# RelayWing.net
KiCad netlist of a schematic drawn in EAGLE
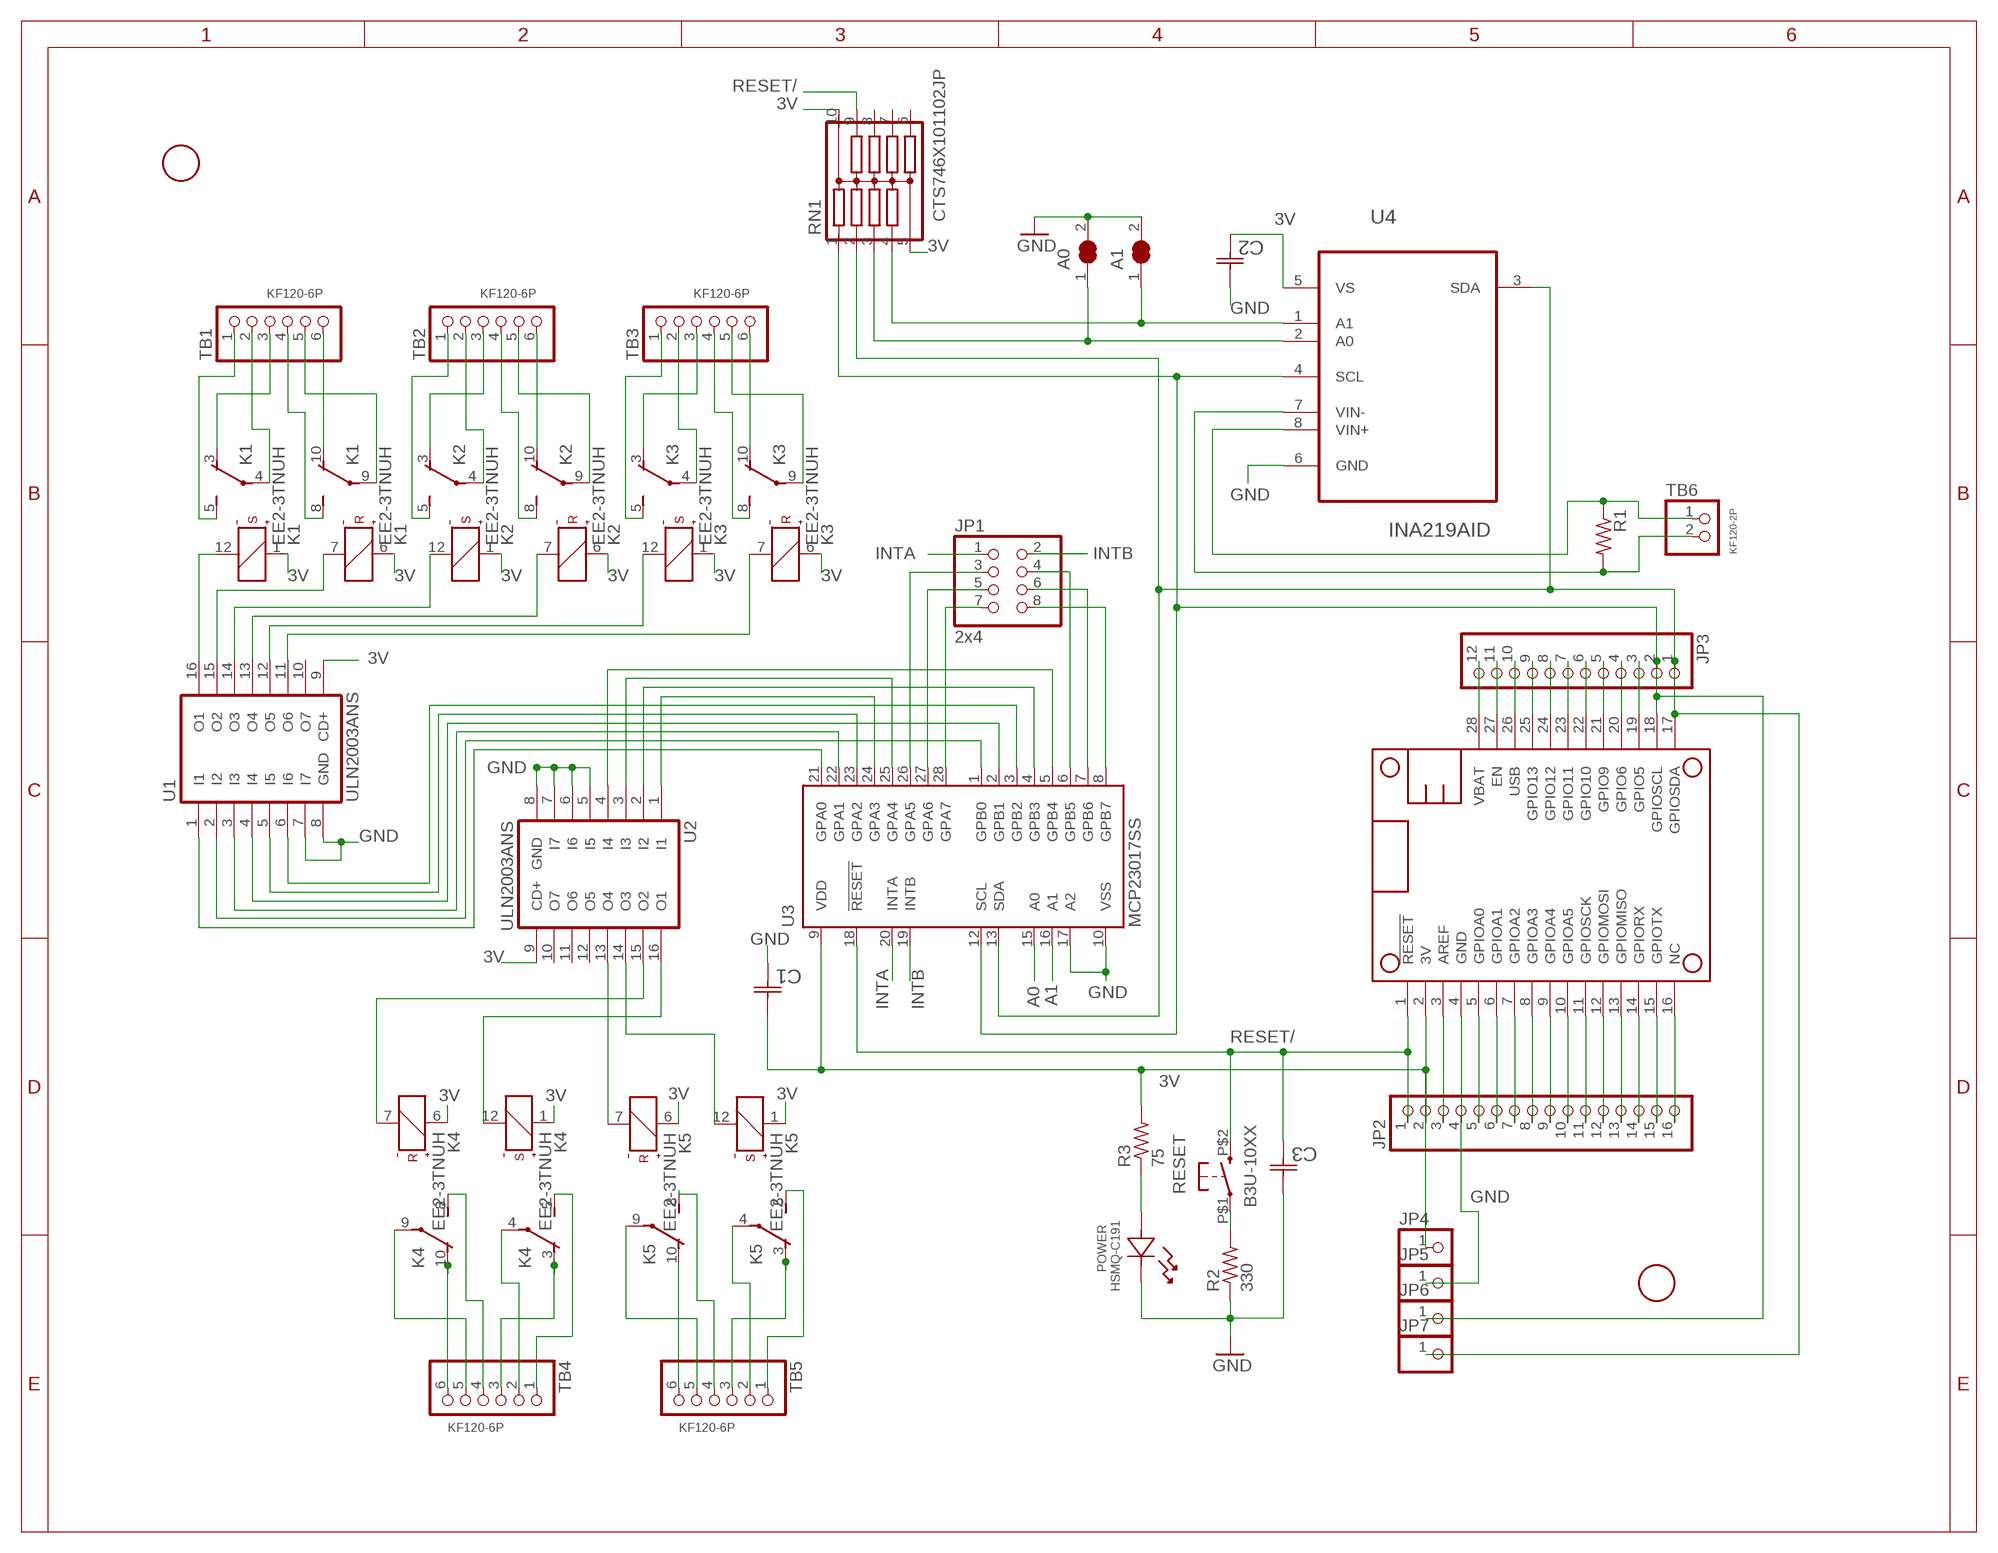
[diagram p0: schematic, sheet 1]

(export (version "E")
  (design (tool "Eeschema 10.0.6"))
  (components
    (comp (ref "A0")
      (value "SJW-SHORTED")
      (footprint "eagle-import:SJW-SHORTED")
      (libsource (lib "eagle-import") (part "SJW-SHORTED"))
    )
    (comp (ref "A1")
      (value "SJW-SHORTED")
      (footprint "eagle-import:SJW-SHORTED")
      (libsource (lib "eagle-import") (part "SJW-SHORTED"))
    )
    (comp (ref "C1")
      (value "MUR-1220-CAP")
      (footprint "eagle-import:CAPC2012")
      (libsource (lib "eagle-import") (part "MUR-1220-CAP"))
    )
    (comp (ref "C2")
      (value "MUR-1220-CAP")
      (footprint "eagle-import:CAPC2012")
      (libsource (lib "eagle-import") (part "MUR-1220-CAP"))
    )
    (comp (ref "C3")
      (value "MUR-1220-CAP")
      (footprint "eagle-import:CAPC2012")
      (libsource (lib "eagle-import") (part "MUR-1220-CAP"))
    )
    (comp (ref "JP1")
      (value "2x4")
      (footprint "eagle-import:2X04")
      (libsource (lib "eagle-import") (part "PINHD-2X4"))
    )
    (comp (ref "JP2")
      (value "PINHD-1X16")
      (footprint "eagle-import:1X16")
      (libsource (lib "eagle-import") (part "PINHD-1X16"))
    )
    (comp (ref "JP3")
      (value "PINHD-1X12")
      (footprint "eagle-import:1X12")
      (libsource (lib "eagle-import") (part "PINHD-1X12"))
    )
    (comp (ref "JP4")
      (value "PINHD-1X1CB")
      (footprint "eagle-import:1X01-CLEANBIG")
      (libsource (lib "eagle-import") (part "PINHD-1X1CB"))
    )
    (comp (ref "JP5")
      (value "PINHD-1X1CB")
      (footprint "eagle-import:1X01-CLEANBIG")
      (libsource (lib "eagle-import") (part "PINHD-1X1CB"))
    )
    (comp (ref "JP6")
      (value "PINHD-1X1CB")
      (footprint "eagle-import:1X01-CLEANBIG")
      (libsource (lib "eagle-import") (part "PINHD-1X1CB"))
    )
    (comp (ref "JP7")
      (value "PINHD-1X1CB")
      (footprint "eagle-import:1X01-CLEANBIG")
      (libsource (lib "eagle-import") (part "PINHD-1X1CB"))
    )
    (comp (ref "K1")
      (value "EE2-3TNUH")
      (footprint "eagle-import:NUH")
      (libsource (lib "eagle-import") (part "EE2-T?NUH3"))
    )
    (comp (ref "K2")
      (value "EE2-3TNUH")
      (footprint "eagle-import:NUH")
      (libsource (lib "eagle-import") (part "EE2-T?NUH3"))
    )
    (comp (ref "K3")
      (value "EE2-3TNUH")
      (footprint "eagle-import:NUH")
      (libsource (lib "eagle-import") (part "EE2-T?NUH3"))
    )
    (comp (ref "K4")
      (value "EE2-3TNUH")
      (footprint "eagle-import:NUH")
      (libsource (lib "eagle-import") (part "EE2-T?NUH3"))
    )
    (comp (ref "K5")
      (value "EE2-3TNUH")
      (footprint "eagle-import:NUH")
      (libsource (lib "eagle-import") (part "EE2-T?NUH3"))
    )
    (comp (ref "MS1")
      (value "FEATHERWING_NODIM")
      (footprint "eagle-import:FEATHERWING_DIM")
      (libsource (lib "eagle-import") (part "FEATHERWING_NODIM"))
    )
    (comp (ref "POWER")
      (value "HSMQ-C191")
      (footprint "eagle-import:LED3_HSMX-C120")
      (fields (field (name "MANUFACTURER_PART_NUMBER") "HSMQC191"))
      (libsource (lib "eagle-import") (part "HSMQ-C191"))
    )
    (comp (ref "R1")
      (value "0.1")
      (footprint "eagle-import:M3216")
      (libsource (lib "eagle-import") (part "resistor_348_R-US_M3216"))
    )
    (comp (ref "R2")
      (value "330")
      (footprint "eagle-import:R0603")
      (libsource (lib "eagle-import") (part "R-US_R0603"))
    )
    (comp (ref "R3")
      (value "75")
      (footprint "eagle-import:R0603")
      (libsource (lib "eagle-import") (part "R-US_R0603"))
    )
    (comp (ref "RESET")
      (value "B3U-10XX")
      (footprint "eagle-import:B3U-10XX")
      (libsource (lib "eagle-import") (part "B3U-10XX"))
    )
    (comp (ref "RN1")
      (value "CTS746X101102JP")
      (footprint "eagle-import:CTS746X101")
      (libsource (lib "eagle-import") (part "CTS746X"))
    )
    (comp (ref "TB1")
      (value "KF120-6P")
      (footprint "eagle-import:KF120-6P_ROUND")
      (libsource (lib "eagle-import") (part "KF120-6P"))
    )
    (comp (ref "TB2")
      (value "KF120-6P")
      (footprint "eagle-import:KF120-6P_ROUND")
      (libsource (lib "eagle-import") (part "KF120-6P"))
    )
    (comp (ref "TB3")
      (value "KF120-6P")
      (footprint "eagle-import:KF120-6P_ROUND")
      (libsource (lib "eagle-import") (part "KF120-6P"))
    )
    (comp (ref "TB4")
      (value "KF120-6P")
      (footprint "eagle-import:KF120-6P_ROUND")
      (libsource (lib "eagle-import") (part "KF120-6P"))
    )
    (comp (ref "TB5")
      (value "KF120-6P")
      (footprint "eagle-import:KF120-6P_ROUND")
      (libsource (lib "eagle-import") (part "KF120-6P"))
    )
    (comp (ref "TB6")
      (value "KF120-2P")
      (footprint "eagle-import:KF120-2P_ROUND")
      (libsource (lib "eagle-import") (part "KF120-2P"))
    )
    (comp (ref "U$2")
      (value "FIDUCIAL")
      (footprint "eagle-import:FIDUCIAL_1MM")
      (libsource (lib "eagle-import") (part "FIDUCIAL"))
    )
    (comp (ref "U$3")
      (value "FIDUCIAL")
      (footprint "eagle-import:FIDUCIAL_1MM")
      (libsource (lib "eagle-import") (part "FIDUCIAL"))
    )
    (comp (ref "U1")
      (value "ULN2003ANS")
      (footprint "eagle-import:SO16-NS")
      (libsource (lib "eagle-import") (part "ULN2003ANS"))
    )
    (comp (ref "U2")
      (value "ULN2003ANS")
      (footprint "eagle-import:SO16-NS")
      (libsource (lib "eagle-import") (part "ULN2003ANS"))
    )
    (comp (ref "U3")
      (value "MCP23017SS")
      (footprint "eagle-import:SSOP28")
      (fields (field (name "MF") "MICROCHIP") (field (name "MPN") "MCP23017-E/SS"))
      (libsource (lib "eagle-import") (part "MCP23017SS"))
    )
    (comp (ref "U4")
      (value "INA219AID")
      (footprint "eagle-import:SOIC127P600X175-8N")
      (libsource (lib "eagle-import") (part "INA219AID"))
    )
  )
  (nets
    (net (code "1") (name "/3V") (class "Default")
      (node (ref "C1") (pin "1") (pinfunction "C1_1") (pintype "passive"))
      (node (ref "C2") (pin "2") (pinfunction "C2_2") (pintype "passive"))
      (node (ref "JP2") (pin "2") (pinfunction "2_2") (pintype "passive"))
      (node (ref "JP4") (pin "1") (pinfunction "1_1") (pintype "passive"))
      (node (ref "K1") (pin "1") (pinfunction "+_1") (pintype "passive"))
      (node (ref "K1") (pin "6") (pinfunction "+_6") (pintype "passive"))
      (node (ref "K2") (pin "1") (pinfunction "+_1") (pintype "passive"))
      (node (ref "K2") (pin "6") (pinfunction "+_6") (pintype "passive"))
      (node (ref "K3") (pin "1") (pinfunction "+_1") (pintype "passive"))
      (node (ref "K3") (pin "6") (pinfunction "+_6") (pintype "passive"))
      (node (ref "K4") (pin "1") (pinfunction "+_1") (pintype "passive"))
      (node (ref "K4") (pin "6") (pinfunction "+_6") (pintype "passive"))
      (node (ref "K5") (pin "1") (pinfunction "+_1") (pintype "passive"))
      (node (ref "K5") (pin "6") (pinfunction "+_6") (pintype "passive"))
      (node (ref "MS1") (pin "2") (pinfunction "3V_2") (pintype "power_in"))
      (node (ref "R3") (pin "2") (pinfunction "2_2") (pintype "passive"))
      (node (ref "RN1") (pin "10") (pinfunction "10C_10") (pintype "passive"))
      (node (ref "RN1") (pin "5") (pinfunction "5C_5") (pintype "passive"))
      (node (ref "U1") (pin "9") (pinfunction "CD+_9") (pintype "passive"))
      (node (ref "U2") (pin "9") (pinfunction "CD+_9") (pintype "passive"))
      (node (ref "U3") (pin "9") (pinfunction "VDD_9") (pintype "power_in"))
      (node (ref "U4") (pin "5") (pinfunction "VS_5") (pintype "power_in"))
    )
    (net (code "2") (name "/A0") (class "Default")
      (node (ref "A0") (pin "1") (pinfunction "1_1") (pintype "passive"))
      (node (ref "RN1") (pin "3") (pinfunction "3_3") (pintype "passive"))
      (node (ref "U3") (pin "15") (pinfunction "A0_15") (pintype "input"))
      (node (ref "U4") (pin "2") (pinfunction "A0_2") (pintype "input"))
    )
    (net (code "3") (name "/A1") (class "Default")
      (node (ref "A1") (pin "1") (pinfunction "1_1") (pintype "passive"))
      (node (ref "RN1") (pin "4") (pinfunction "4_4") (pintype "passive"))
      (node (ref "U3") (pin "16") (pinfunction "A1_16") (pintype "input"))
      (node (ref "U4") (pin "1") (pinfunction "A1_1") (pintype "input"))
    )
    (net (code "4") (name "/INTA") (class "Default")
      (node (ref "JP1") (pin "1") (pinfunction "1_1") (pintype "passive"))
      (node (ref "U3") (pin "20") (pinfunction "INTA_20") (pintype "output"))
    )
    (net (code "5") (name "/INTB") (class "Default")
      (node (ref "JP1") (pin "2") (pinfunction "2_2") (pintype "passive"))
      (node (ref "U3") (pin "19") (pinfunction "INTB_19") (pintype "output"))
    )
    (net (code "6") (name "/RESET{slash}") (class "Default")
      (node (ref "C3") (pin "2") (pinfunction "C2_2") (pintype "passive"))
      (node (ref "JP2") (pin "1") (pinfunction "1_1") (pintype "passive"))
      (node (ref "MS1") (pin "1") (pinfunction "~{RESET}_1") (pintype "input"))
      (node (ref "RESET") (pin "P$2") (pinfunction "S_P$2") (pintype "passive"))
      (node (ref "RN1") (pin "9") (pinfunction "9_9") (pintype "passive"))
      (node (ref "U3") (pin "18") (pinfunction "~{RESET}_18") (pintype "input"))
    )
    (net (code "7") (name "GND") (class "Default")
      (node (ref "A0") (pin "2") (pinfunction "2_2") (pintype "passive"))
      (node (ref "A1") (pin "2") (pinfunction "2_2") (pintype "passive"))
      (node (ref "C1") (pin "2") (pinfunction "C2_2") (pintype "passive"))
      (node (ref "C2") (pin "1") (pinfunction "C1_1") (pintype "passive"))
      (node (ref "C3") (pin "1") (pinfunction "C1_1") (pintype "passive"))
      (node (ref "JP2") (pin "4") (pinfunction "4_4") (pintype "passive"))
      (node (ref "JP5") (pin "1") (pinfunction "1_1") (pintype "passive"))
      (node (ref "MS1") (pin "4") (pinfunction "GND_4") (pintype "power_in"))
      (node (ref "POWER") (pin "1") (pinfunction "11_1") (pintype "passive"))
      (node (ref "R2") (pin "1") (pinfunction "1_1") (pintype "passive"))
      (node (ref "U1") (pin "7") (pinfunction "I7_7") (pintype "input"))
      (node (ref "U1") (pin "8") (pinfunction "GND_8") (pintype "power_in"))
      (node (ref "U2") (pin "5") (pinfunction "I5_5") (pintype "input"))
      (node (ref "U2") (pin "6") (pinfunction "I6_6") (pintype "input"))
      (node (ref "U2") (pin "7") (pinfunction "I7_7") (pintype "input"))
      (node (ref "U2") (pin "8") (pinfunction "GND_8") (pintype "power_in"))
      (node (ref "U3") (pin "10") (pinfunction "VSS_10") (pintype "power_in"))
      (node (ref "U3") (pin "17") (pinfunction "A2_17") (pintype "input"))
      (node (ref "U4") (pin "6") (pinfunction "GND_6") (pintype "passive"))
    )
    (net (code "8") (name "Net-(K1A-O)") (class "Default")
      (node (ref "K1") (pin "3") (pinfunction "O_3") (pintype "passive"))
      (node (ref "TB1") (pin "3") (pinfunction "3_3") (pintype "passive"))
    )
    (net (code "9") (name "Net-(K1A-P)") (class "Default")
      (node (ref "K1") (pin "4") (pinfunction "P_4") (pintype "passive"))
      (node (ref "TB1") (pin "2") (pinfunction "2_2") (pintype "passive"))
    )
    (net (code "10") (name "Net-(K1A-S)") (class "Default")
      (node (ref "K1") (pin "5") (pinfunction "S_5") (pintype "passive"))
      (node (ref "TB1") (pin "1") (pinfunction "1_1") (pintype "passive"))
    )
    (net (code "11") (name "Net-(K1B-O)") (class "Default")
      (node (ref "K1") (pin "10") (pinfunction "O_10") (pintype "passive"))
      (node (ref "TB1") (pin "6") (pinfunction "6_6") (pintype "passive"))
    )
    (net (code "12") (name "Net-(K1B-P)") (class "Default")
      (node (ref "K1") (pin "9") (pinfunction "P_9") (pintype "passive"))
      (node (ref "TB1") (pin "5") (pinfunction "5_5") (pintype "passive"))
    )
    (net (code "13") (name "Net-(K1B-S)") (class "Default")
      (node (ref "K1") (pin "8") (pinfunction "S_8") (pintype "passive"))
      (node (ref "TB1") (pin "4") (pinfunction "4_4") (pintype "passive"))
    )
    (net (code "14") (name "Net-(K1C--)") (class "Default")
      (node (ref "K1") (pin "7") (pinfunction "-_7") (pintype "passive"))
      (node (ref "U1") (pin "15") (pinfunction "O2_15") (pintype "open_collector"))
    )
    (net (code "15") (name "Net-(K1D--)") (class "Default")
      (node (ref "K1") (pin "12") (pinfunction "-_12") (pintype "passive"))
      (node (ref "U1") (pin "16") (pinfunction "O1_16") (pintype "open_collector"))
    )
    (net (code "16") (name "Net-(K2A-O)") (class "Default")
      (node (ref "K2") (pin "3") (pinfunction "O_3") (pintype "passive"))
      (node (ref "TB2") (pin "3") (pinfunction "3_3") (pintype "passive"))
    )
    (net (code "17") (name "Net-(K2A-P)") (class "Default")
      (node (ref "K2") (pin "4") (pinfunction "P_4") (pintype "passive"))
      (node (ref "TB2") (pin "2") (pinfunction "2_2") (pintype "passive"))
    )
    (net (code "18") (name "Net-(K2A-S)") (class "Default")
      (node (ref "K2") (pin "5") (pinfunction "S_5") (pintype "passive"))
      (node (ref "TB2") (pin "1") (pinfunction "1_1") (pintype "passive"))
    )
    (net (code "19") (name "Net-(K2B-O)") (class "Default")
      (node (ref "K2") (pin "10") (pinfunction "O_10") (pintype "passive"))
      (node (ref "TB2") (pin "6") (pinfunction "6_6") (pintype "passive"))
    )
    (net (code "20") (name "Net-(K2B-P)") (class "Default")
      (node (ref "K2") (pin "9") (pinfunction "P_9") (pintype "passive"))
      (node (ref "TB2") (pin "5") (pinfunction "5_5") (pintype "passive"))
    )
    (net (code "21") (name "Net-(K2B-S)") (class "Default")
      (node (ref "K2") (pin "8") (pinfunction "S_8") (pintype "passive"))
      (node (ref "TB2") (pin "4") (pinfunction "4_4") (pintype "passive"))
    )
    (net (code "22") (name "Net-(K2C--)") (class "Default")
      (node (ref "K2") (pin "7") (pinfunction "-_7") (pintype "passive"))
      (node (ref "U1") (pin "13") (pinfunction "O4_13") (pintype "open_collector"))
    )
    (net (code "23") (name "Net-(K2D--)") (class "Default")
      (node (ref "K2") (pin "12") (pinfunction "-_12") (pintype "passive"))
      (node (ref "U1") (pin "14") (pinfunction "O3_14") (pintype "open_collector"))
    )
    (net (code "24") (name "Net-(K3A-O)") (class "Default")
      (node (ref "K3") (pin "3") (pinfunction "O_3") (pintype "passive"))
      (node (ref "TB3") (pin "3") (pinfunction "3_3") (pintype "passive"))
    )
    (net (code "25") (name "Net-(K3A-P)") (class "Default")
      (node (ref "K3") (pin "4") (pinfunction "P_4") (pintype "passive"))
      (node (ref "TB3") (pin "2") (pinfunction "2_2") (pintype "passive"))
    )
    (net (code "26") (name "Net-(K3A-S)") (class "Default")
      (node (ref "K3") (pin "5") (pinfunction "S_5") (pintype "passive"))
      (node (ref "TB3") (pin "1") (pinfunction "1_1") (pintype "passive"))
    )
    (net (code "27") (name "Net-(K3B-O)") (class "Default")
      (node (ref "K3") (pin "10") (pinfunction "O_10") (pintype "passive"))
      (node (ref "TB3") (pin "6") (pinfunction "6_6") (pintype "passive"))
    )
    (net (code "28") (name "Net-(K3B-P)") (class "Default")
      (node (ref "K3") (pin "9") (pinfunction "P_9") (pintype "passive"))
      (node (ref "TB3") (pin "5") (pinfunction "5_5") (pintype "passive"))
    )
    (net (code "29") (name "Net-(K3B-S)") (class "Default")
      (node (ref "K3") (pin "8") (pinfunction "S_8") (pintype "passive"))
      (node (ref "TB3") (pin "4") (pinfunction "4_4") (pintype "passive"))
    )
    (net (code "30") (name "Net-(K3C--)") (class "Default")
      (node (ref "K3") (pin "7") (pinfunction "-_7") (pintype "passive"))
      (node (ref "U1") (pin "11") (pinfunction "O6_11") (pintype "open_collector"))
    )
    (net (code "31") (name "Net-(K3D--)") (class "Default")
      (node (ref "K3") (pin "12") (pinfunction "-_12") (pintype "passive"))
      (node (ref "U1") (pin "12") (pinfunction "O5_12") (pintype "open_collector"))
    )
    (net (code "32") (name "Net-(K4A-O)") (class "Default")
      (node (ref "K4") (pin "3") (pinfunction "O_3") (pintype "passive"))
      (node (ref "TB4") (pin "3") (pinfunction "3_3") (pintype "passive"))
    )
    (net (code "33") (name "Net-(K4A-P)") (class "Default")
      (node (ref "K4") (pin "4") (pinfunction "P_4") (pintype "passive"))
      (node (ref "TB4") (pin "2") (pinfunction "2_2") (pintype "passive"))
    )
    (net (code "34") (name "Net-(K4A-S)") (class "Default")
      (node (ref "K4") (pin "5") (pinfunction "S_5") (pintype "passive"))
      (node (ref "TB4") (pin "1") (pinfunction "1_1") (pintype "passive"))
    )
    (net (code "35") (name "Net-(K4B-O)") (class "Default")
      (node (ref "K4") (pin "10") (pinfunction "O_10") (pintype "passive"))
      (node (ref "TB4") (pin "6") (pinfunction "6_6") (pintype "passive"))
    )
    (net (code "36") (name "Net-(K4B-P)") (class "Default")
      (node (ref "K4") (pin "9") (pinfunction "P_9") (pintype "passive"))
      (node (ref "TB4") (pin "5") (pinfunction "5_5") (pintype "passive"))
    )
    (net (code "37") (name "Net-(K4B-S)") (class "Default")
      (node (ref "K4") (pin "8") (pinfunction "S_8") (pintype "passive"))
      (node (ref "TB4") (pin "4") (pinfunction "4_4") (pintype "passive"))
    )
    (net (code "38") (name "Net-(K4C--)") (class "Default")
      (node (ref "K4") (pin "7") (pinfunction "-_7") (pintype "passive"))
      (node (ref "U2") (pin "15") (pinfunction "O2_15") (pintype "open_collector"))
    )
    (net (code "39") (name "Net-(K4D--)") (class "Default")
      (node (ref "K4") (pin "12") (pinfunction "-_12") (pintype "passive"))
      (node (ref "U2") (pin "16") (pinfunction "O1_16") (pintype "open_collector"))
    )
    (net (code "40") (name "Net-(K5A-O)") (class "Default")
      (node (ref "K5") (pin "3") (pinfunction "O_3") (pintype "passive"))
      (node (ref "TB5") (pin "3") (pinfunction "3_3") (pintype "passive"))
    )
    (net (code "41") (name "Net-(K5A-P)") (class "Default")
      (node (ref "K5") (pin "4") (pinfunction "P_4") (pintype "passive"))
      (node (ref "TB5") (pin "2") (pinfunction "2_2") (pintype "passive"))
    )
    (net (code "42") (name "Net-(K5A-S)") (class "Default")
      (node (ref "K5") (pin "5") (pinfunction "S_5") (pintype "passive"))
      (node (ref "TB5") (pin "1") (pinfunction "1_1") (pintype "passive"))
    )
    (net (code "43") (name "Net-(K5B-O)") (class "Default")
      (node (ref "K5") (pin "10") (pinfunction "O_10") (pintype "passive"))
      (node (ref "TB5") (pin "6") (pinfunction "6_6") (pintype "passive"))
    )
    (net (code "44") (name "Net-(K5B-P)") (class "Default")
      (node (ref "K5") (pin "9") (pinfunction "P_9") (pintype "passive"))
      (node (ref "TB5") (pin "5") (pinfunction "5_5") (pintype "passive"))
    )
    (net (code "45") (name "Net-(K5B-S)") (class "Default")
      (node (ref "K5") (pin "8") (pinfunction "S_8") (pintype "passive"))
      (node (ref "TB5") (pin "4") (pinfunction "4_4") (pintype "passive"))
    )
    (net (code "46") (name "Net-(K5C--)") (class "Default")
      (node (ref "K5") (pin "7") (pinfunction "-_7") (pintype "passive"))
      (node (ref "U2") (pin "13") (pinfunction "O4_13") (pintype "open_collector"))
    )
    (net (code "47") (name "Net-(K5D--)") (class "Default")
      (node (ref "K5") (pin "12") (pinfunction "-_12") (pintype "passive"))
      (node (ref "U2") (pin "14") (pinfunction "O3_14") (pintype "open_collector"))
    )
    (net (code "48") (name "Net-(MS1-AREF)") (class "Default")
      (node (ref "JP2") (pin "3") (pinfunction "3_3") (pintype "passive"))
      (node (ref "MS1") (pin "3") (pinfunction "AREF_3") (pintype "passive"))
    )
    (net (code "49") (name "Net-(MS1-EN)") (class "Default")
      (node (ref "JP3") (pin "11") (pinfunction "11_11") (pintype "passive"))
      (node (ref "MS1") (pin "27") (pinfunction "EN_27") (pintype "passive"))
    )
    (net (code "50") (name "Net-(MS1-GPIO5)") (class "Default")
      (node (ref "JP3") (pin "3") (pinfunction "3_3") (pintype "passive"))
      (node (ref "MS1") (pin "19") (pinfunction "GPIO5_19") (pintype "bidirectional"))
    )
    (net (code "51") (name "Net-(MS1-GPIO6)") (class "Default")
      (node (ref "JP3") (pin "4") (pinfunction "4_4") (pintype "passive"))
      (node (ref "MS1") (pin "20") (pinfunction "GPIO6_20") (pintype "bidirectional"))
    )
    (net (code "52") (name "Net-(MS1-GPIO9)") (class "Default")
      (node (ref "JP3") (pin "5") (pinfunction "5_5") (pintype "passive"))
      (node (ref "MS1") (pin "21") (pinfunction "GPIO9_21") (pintype "bidirectional"))
    )
    (net (code "53") (name "Net-(MS1-GPIO10)") (class "Default")
      (node (ref "JP3") (pin "6") (pinfunction "6_6") (pintype "passive"))
      (node (ref "MS1") (pin "22") (pinfunction "GPIO10_22") (pintype "bidirectional"))
    )
    (net (code "54") (name "Net-(MS1-GPIO11)") (class "Default")
      (node (ref "JP3") (pin "7") (pinfunction "7_7") (pintype "passive"))
      (node (ref "MS1") (pin "23") (pinfunction "GPIO11_23") (pintype "bidirectional"))
    )
    (net (code "55") (name "Net-(MS1-GPIO12)") (class "Default")
      (node (ref "JP3") (pin "8") (pinfunction "8_8") (pintype "passive"))
      (node (ref "MS1") (pin "24") (pinfunction "GPIO12_24") (pintype "bidirectional"))
    )
    (net (code "56") (name "Net-(MS1-GPIO13)") (class "Default")
      (node (ref "JP3") (pin "9") (pinfunction "9_9") (pintype "passive"))
      (node (ref "MS1") (pin "25") (pinfunction "GPIO13_25") (pintype "bidirectional"))
    )
    (net (code "57") (name "Net-(MS1-GPIOA0)") (class "Default")
      (node (ref "JP2") (pin "5") (pinfunction "5_5") (pintype "passive"))
      (node (ref "MS1") (pin "5") (pinfunction "GPIOA0_5") (pintype "bidirectional"))
    )
    (net (code "58") (name "Net-(MS1-GPIOA1)") (class "Default")
      (node (ref "JP2") (pin "6") (pinfunction "6_6") (pintype "passive"))
      (node (ref "MS1") (pin "6") (pinfunction "GPIOA1_6") (pintype "bidirectional"))
    )
    (net (code "59") (name "Net-(MS1-GPIOA2)") (class "Default")
      (node (ref "JP2") (pin "7") (pinfunction "7_7") (pintype "passive"))
      (node (ref "MS1") (pin "7") (pinfunction "GPIOA2_7") (pintype "bidirectional"))
    )
    (net (code "60") (name "Net-(MS1-GPIOA3)") (class "Default")
      (node (ref "JP2") (pin "8") (pinfunction "8_8") (pintype "passive"))
      (node (ref "MS1") (pin "8") (pinfunction "GPIOA3_8") (pintype "bidirectional"))
    )
    (net (code "61") (name "Net-(MS1-GPIOA4)") (class "Default")
      (node (ref "JP2") (pin "9") (pinfunction "9_9") (pintype "passive"))
      (node (ref "MS1") (pin "9") (pinfunction "GPIOA4_9") (pintype "bidirectional"))
    )
    (net (code "62") (name "Net-(MS1-GPIOA5)") (class "Default")
      (node (ref "JP2") (pin "10") (pinfunction "10_10") (pintype "passive"))
      (node (ref "MS1") (pin "10") (pinfunction "GPIOA5_10") (pintype "bidirectional"))
    )
    (net (code "63") (name "Net-(MS1-GPIOMISO)") (class "Default")
      (node (ref "JP2") (pin "13") (pinfunction "13_13") (pintype "passive"))
      (node (ref "MS1") (pin "13") (pinfunction "GPIOMISO_13") (pintype "bidirectional"))
    )
    (net (code "64") (name "Net-(MS1-GPIOMOSI)") (class "Default")
      (node (ref "JP2") (pin "12") (pinfunction "12_12") (pintype "passive"))
      (node (ref "MS1") (pin "12") (pinfunction "GPIOMOSI_12") (pintype "bidirectional"))
    )
    (net (code "65") (name "Net-(MS1-GPIORX)") (class "Default")
      (node (ref "JP2") (pin "14") (pinfunction "14_14") (pintype "passive"))
      (node (ref "MS1") (pin "14") (pinfunction "GPIORX_14") (pintype "bidirectional"))
    )
    (net (code "66") (name "Net-(MS1-GPIOSCK)") (class "Default")
      (node (ref "JP2") (pin "11") (pinfunction "11_11") (pintype "passive"))
      (node (ref "MS1") (pin "11") (pinfunction "GPIOSCK_11") (pintype "bidirectional"))
    )
    (net (code "67") (name "Net-(MS1-GPIOSCL)") (class "Default")
      (node (ref "JP3") (pin "2") (pinfunction "2_2") (pintype "passive"))
      (node (ref "JP6") (pin "1") (pinfunction "1_1") (pintype "passive"))
      (node (ref "MS1") (pin "18") (pinfunction "GPIOSCL_18") (pintype "bidirectional"))
      (node (ref "RN1") (pin "1") (pinfunction "1_1") (pintype "passive"))
      (node (ref "U3") (pin "12") (pinfunction "SCL_12") (pintype "input"))
      (node (ref "U4") (pin "4") (pinfunction "SCL_4") (pintype "input"))
    )
    (net (code "68") (name "Net-(MS1-GPIOSDA)") (class "Default")
      (node (ref "JP3") (pin "1") (pinfunction "1_1") (pintype "passive"))
      (node (ref "JP7") (pin "1") (pinfunction "1_1") (pintype "passive"))
      (node (ref "MS1") (pin "17") (pinfunction "GPIOSDA_17") (pintype "bidirectional"))
      (node (ref "RN1") (pin "2") (pinfunction "2_2") (pintype "passive"))
      (node (ref "U3") (pin "13") (pinfunction "SDA_13") (pintype "bidirectional"))
      (node (ref "U4") (pin "3") (pinfunction "SDA_3") (pintype "bidirectional"))
    )
    (net (code "69") (name "Net-(MS1-GPIOTX)") (class "Default")
      (node (ref "JP2") (pin "15") (pinfunction "15_15") (pintype "passive"))
      (node (ref "MS1") (pin "15") (pinfunction "GPIOTX_15") (pintype "bidirectional"))
    )
    (net (code "70") (name "Net-(MS1-NC)") (class "Default")
      (node (ref "JP2") (pin "16") (pinfunction "16_16") (pintype "passive"))
      (node (ref "MS1") (pin "16") (pinfunction "NC_16") (pintype "passive"))
    )
    (net (code "71") (name "Net-(MS1-USB)") (class "Default")
      (node (ref "JP3") (pin "10") (pinfunction "10_10") (pintype "passive"))
      (node (ref "MS1") (pin "26") (pinfunction "USB_26") (pintype "power_in"))
    )
    (net (code "72") (name "Net-(MS1-VBAT)") (class "Default")
      (node (ref "JP3") (pin "12") (pinfunction "12_12") (pintype "passive"))
      (node (ref "MS1") (pin "28") (pinfunction "VBAT_28") (pintype "power_in"))
    )
    (net (code "73") (name "Net-(POWER-33)") (class "Default")
      (node (ref "POWER") (pin "2") (pinfunction "33_2") (pintype "passive"))
      (node (ref "R3") (pin "1") (pinfunction "1_1") (pintype "passive"))
    )
    (net (code "74") (name "Net-(RESET-P)") (class "Default")
      (node (ref "R2") (pin "2") (pinfunction "2_2") (pintype "passive"))
      (node (ref "RESET") (pin "P$1") (pinfunction "P_P$1") (pintype "passive"))
    )
    (net (code "75") (name "Net-(U1-I1)") (class "Default")
      (node (ref "U1") (pin "1") (pinfunction "I1_1") (pintype "input"))
      (node (ref "U3") (pin "21") (pinfunction "GPA0_21") (pintype "bidirectional"))
    )
    (net (code "76") (name "Net-(U1-I2)") (class "Default")
      (node (ref "U1") (pin "2") (pinfunction "I2_2") (pintype "input"))
      (node (ref "U3") (pin "1") (pinfunction "GPB0_1") (pintype "bidirectional"))
    )
    (net (code "77") (name "Net-(U1-I3)") (class "Default")
      (node (ref "U1") (pin "3") (pinfunction "I3_3") (pintype "input"))
      (node (ref "U3") (pin "22") (pinfunction "GPA1_22") (pintype "bidirectional"))
    )
    (net (code "78") (name "Net-(U1-I4)") (class "Default")
      (node (ref "U1") (pin "4") (pinfunction "I4_4") (pintype "input"))
      (node (ref "U3") (pin "2") (pinfunction "GPB1_2") (pintype "bidirectional"))
    )
    (net (code "79") (name "Net-(U1-I5)") (class "Default")
      (node (ref "U1") (pin "5") (pinfunction "I5_5") (pintype "input"))
      (node (ref "U3") (pin "23") (pinfunction "GPA2_23") (pintype "bidirectional"))
    )
    (net (code "80") (name "Net-(U1-I6)") (class "Default")
      (node (ref "U1") (pin "6") (pinfunction "I6_6") (pintype "input"))
      (node (ref "U3") (pin "3") (pinfunction "GPB2_3") (pintype "bidirectional"))
    )
    (net (code "81") (name "Net-(U2-I1)") (class "Default")
      (node (ref "U2") (pin "1") (pinfunction "I1_1") (pintype "input"))
      (node (ref "U3") (pin "24") (pinfunction "GPA3_24") (pintype "bidirectional"))
    )
    (net (code "82") (name "Net-(U2-I2)") (class "Default")
      (node (ref "U2") (pin "2") (pinfunction "I2_2") (pintype "input"))
      (node (ref "U3") (pin "4") (pinfunction "GPB3_4") (pintype "bidirectional"))
    )
    (net (code "83") (name "Net-(U2-I3)") (class "Default")
      (node (ref "U2") (pin "3") (pinfunction "I3_3") (pintype "input"))
      (node (ref "U3") (pin "25") (pinfunction "GPA4_25") (pintype "bidirectional"))
    )
    (net (code "84") (name "Net-(U2-I4)") (class "Default")
      (node (ref "U2") (pin "4") (pinfunction "I4_4") (pintype "input"))
      (node (ref "U3") (pin "5") (pinfunction "GPB4_5") (pintype "bidirectional"))
    )
    (net (code "85") (name "Net-(U3-GPA5)") (class "Default")
      (node (ref "JP1") (pin "3") (pinfunction "3_3") (pintype "passive"))
      (node (ref "U3") (pin "26") (pinfunction "GPA5_26") (pintype "bidirectional"))
    )
    (net (code "86") (name "Net-(U3-GPA6)") (class "Default")
      (node (ref "JP1") (pin "5") (pinfunction "5_5") (pintype "passive"))
      (node (ref "U3") (pin "27") (pinfunction "GPA6_27") (pintype "bidirectional"))
    )
    (net (code "87") (name "Net-(U3-GPA7)") (class "Default")
      (node (ref "JP1") (pin "7") (pinfunction "7_7") (pintype "passive"))
      (node (ref "U3") (pin "28") (pinfunction "GPA7_28") (pintype "bidirectional"))
    )
    (net (code "88") (name "Net-(U3-GPB5)") (class "Default")
      (node (ref "JP1") (pin "4") (pinfunction "4_4") (pintype "passive"))
      (node (ref "U3") (pin "6") (pinfunction "GPB5_6") (pintype "bidirectional"))
    )
    (net (code "89") (name "Net-(U3-GPB6)") (class "Default")
      (node (ref "JP1") (pin "6") (pinfunction "6_6") (pintype "passive"))
      (node (ref "U3") (pin "7") (pinfunction "GPB6_7") (pintype "bidirectional"))
    )
    (net (code "90") (name "Net-(U3-GPB7)") (class "Default")
      (node (ref "JP1") (pin "8") (pinfunction "8_8") (pintype "passive"))
      (node (ref "U3") (pin "8") (pinfunction "GPB7_8") (pintype "bidirectional"))
    )
    (net (code "91") (name "Net-(U4-VIN+)") (class "Default")
      (node (ref "R1") (pin "1") (pinfunction "1_1") (pintype "passive"))
      (node (ref "TB6") (pin "1") (pinfunction "1_1") (pintype "passive"))
      (node (ref "U4") (pin "8") (pinfunction "VIN+_8") (pintype "input"))
    )
    (net (code "92") (name "Net-(U4-VIN-)") (class "Default")
      (node (ref "R1") (pin "2") (pinfunction "2_2") (pintype "passive"))
      (node (ref "TB6") (pin "2") (pinfunction "2_2") (pintype "passive"))
      (node (ref "U4") (pin "7") (pinfunction "VIN-_7") (pintype "input"))
    )
    (net (code "93") (name "unconnected-(RN1-Pad6)") (class "Default")
      (node (ref "RN1") (pin "6") (pinfunction "6_6") (pintype "passive"))
    )
    (net (code "94") (name "unconnected-(RN1-Pad7)") (class "Default")
      (node (ref "RN1") (pin "7") (pinfunction "7_7") (pintype "passive"))
    )
    (net (code "95") (name "unconnected-(RN1-Pad8)") (class "Default")
      (node (ref "RN1") (pin "8") (pinfunction "8_8") (pintype "passive"))
    )
    (net (code "96") (name "unconnected-(U1-O7-Pad10)") (class "Default")
      (node (ref "U1") (pin "10") (pinfunction "O7_10") (pintype "open_collector"))
    )
    (net (code "97") (name "unconnected-(U2-O5-Pad12)") (class "Default")
      (node (ref "U2") (pin "12") (pinfunction "O5_12") (pintype "open_collector"))
    )
    (net (code "98") (name "unconnected-(U2-O6-Pad11)") (class "Default")
      (node (ref "U2") (pin "11") (pinfunction "O6_11") (pintype "open_collector"))
    )
    (net (code "99") (name "unconnected-(U2-O7-Pad10)") (class "Default")
      (node (ref "U2") (pin "10") (pinfunction "O7_10") (pintype "open_collector"))
    )
  )
)
